# DTMF.net
KiCad netlist of a schematic drawn in Altium Designer
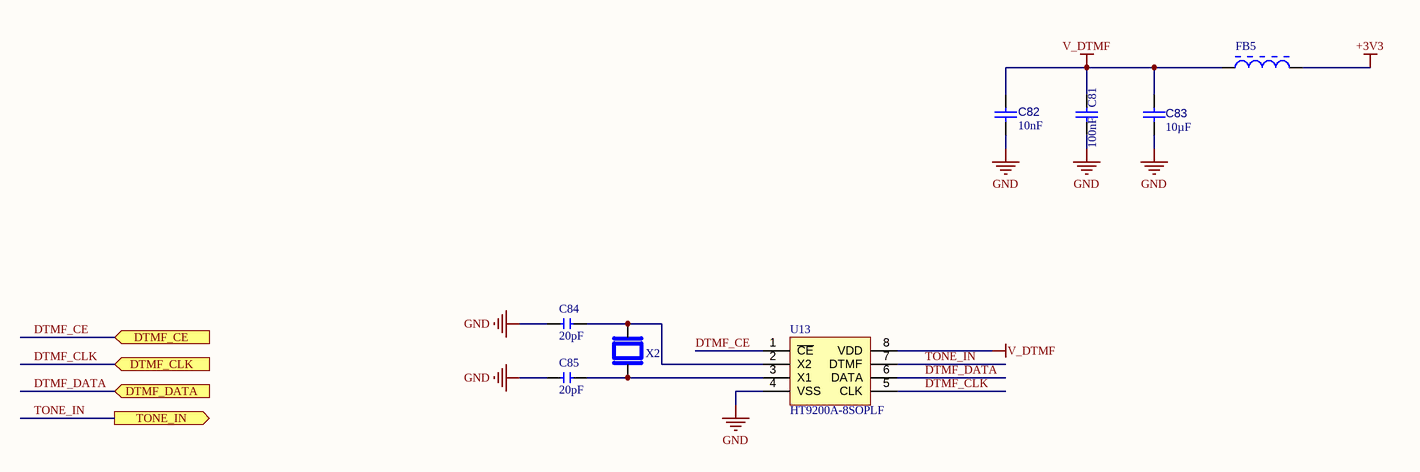
[diagram p0: DTMF.SchDoc]

(export (version "E")
  (design (tool "Eeschema 10.0.6"))
  (components
    (comp (ref "C81")
      (value "100nF")
      (footprint "C0603")
      (description "YAGEO - CC0603KRX7R8BB104 - CERAMIC CAPACITOR, 0.1UF, 25V, X7R, 10%, 0603, FULL REEL")
      (fields
        (field (name "TOLERANCE") "10%")
        (field (name "VOLTAGE") "25V")
        (field (name "SOURCE") "PTZLib.SchLib")
      )
      (libsource (lib "Kish Spark") (part "CAP-NP-2"))
    )
    (comp (ref "C82")
      (value "10nF")
      (footprint "C0603")
      (description "0603 10nF 50 V ±10 % Tolerance X7R Surface Mount Multilayer Ceramic Capacitor")
      (fields (field (name "TOLERANCE") "10%") (field (name "MANUFACTURER") "Kyocera AVX"))
      (libsource (lib "Kish Spark") (part "CAP-NP-2"))
    )
    (comp (ref "C83")
      (value "10µF")
      (footprint "0805")
      (description "Ceramic Capacitor, 10UF, 6.3V, X5R, 10%, 0805, Full Reel")
      (fields
        (field (name "MANUFACTURER") "KEMET")
        (field (name "MANUFACTURER PART NUMBER") "C0805C106K9PACTU")
      )
      (libsource (lib "Kish Spark") (part "CAP-NP-2"))
    )
    (comp (ref "C84")
      (value "20pF")
      (footprint "0805")
      (description "CAP CER 20PF 50V NPO 0805")
      (fields
        (field (name "MANUFACTURER") "Yageo")
        (field (name "MANUFACTURER PART NUMBER") "CC0805JRNPO9BN200")
      )
      (libsource (lib "Kish Spark") (part "CC0805JRNPO9BN200"))
    )
    (comp (ref "C85")
      (value "20pF")
      (footprint "0805")
      (description "CAP CER 20PF 50V NPO 0805")
      (fields
        (field (name "MANUFACTURER") "Yageo")
        (field (name "MANUFACTURER PART NUMBER") "CC0805JRNPO9BN200")
      )
      (libsource (lib "Kish Spark") (part "CC0805JRNPO9BN200"))
    )
    (comp (ref "FB5")
      (value "CMP-006-00051-1")
      (footprint "R0603")
      (description "Ferrite Beads 0603 60ohm")
      (fields (field (name "TOLERANCE") "25%") (field (name "SOURCE") "PTZLib.SchLib"))
      (libsource (lib "Kish Spark") (part "FerriteBead"))
    )
    (comp (ref "U13")
      (value "HT9200A-8SOPLF")
      (footprint "SSOIC8")
      (description "IC, Dtmf Generator, SMD, SOP8")
      (fields (field (name "MANUFACTURER") "Holtek"))
      (libsource (lib "Kish Spark") (part "HT9200A-8SOPLF"))
    )
    (comp (ref "X2")
      (value "CMP-003-00038-1")
      (footprint "XTAL")
      (description "Crystal 3.579545MHz ±30ppm (Tol) ±50ppm (Stability) 18pF FUND 180Ohm 2-Pin HC-49/US SMD T/R")
      (fields
        (field (name "MANUFACTURER") "Abracon")
        (field (name "MANUFACTURER PART NUMBER") "ABLS-3.579545MHZ-B4-T")
      )
      (libsource (lib "Kish Spark") (part "ABLS-3.579545MHZ-B4-T"))
    )
  )
  (nets
    (net (code "1") (name "+3V3") (class "Default")
      (node (ref "FB5") (pin "2") (pinfunction "2_2") (pintype "passive"))
    )
    (net (code "2") (name "/DTMF_CE") (class "Default")
      (node (ref "U13") (pin "1") (pinfunction "~{CE}_1") (pintype "passive"))
    )
    (net (code "3") (name "/DTMF_CLK") (class "Default")
      (node (ref "U13") (pin "5") (pinfunction "CLK_5") (pintype "passive"))
    )
    (net (code "4") (name "/DTMF_DATA") (class "Default")
      (node (ref "U13") (pin "6") (pinfunction "DATA_6") (pintype "passive"))
    )
    (net (code "5") (name "/TONE_IN") (class "Default")
      (node (ref "U13") (pin "7") (pinfunction "DTMF_7") (pintype "passive"))
    )
    (net (code "6") (name "GND") (class "Default")
      (node (ref "C81") (pin "2") (pinfunction "2_2") (pintype "passive"))
      (node (ref "C82") (pin "2") (pinfunction "2_2") (pintype "passive"))
      (node (ref "C83") (pin "1") (pinfunction "1_1") (pintype "passive"))
      (node (ref "C84") (pin "1") (pinfunction "1_1") (pintype "passive"))
      (node (ref "C85") (pin "1") (pinfunction "1_1") (pintype "passive"))
      (node (ref "U13") (pin "4") (pinfunction "VSS_4") (pintype "passive"))
    )
    (net (code "7") (name "Net-(U13-X1)") (class "Default")
      (node (ref "C85") (pin "2") (pinfunction "2_2") (pintype "passive"))
      (node (ref "U13") (pin "3") (pinfunction "X1_3") (pintype "passive"))
      (node (ref "X2") (pin "1") (pinfunction "1_1") (pintype "passive"))
    )
    (net (code "8") (name "Net-(U13-X2)") (class "Default")
      (node (ref "C84") (pin "2") (pinfunction "2_2") (pintype "passive"))
      (node (ref "U13") (pin "2") (pinfunction "X2_2") (pintype "passive"))
      (node (ref "X2") (pin "2") (pinfunction "2_2") (pintype "passive"))
    )
    (net (code "9") (name "V_DTMF") (class "Default")
      (node (ref "C81") (pin "1") (pinfunction "1_1") (pintype "passive"))
      (node (ref "C82") (pin "1") (pinfunction "1_1") (pintype "passive"))
      (node (ref "C83") (pin "2") (pinfunction "2_2") (pintype "passive"))
      (node (ref "FB5") (pin "1") (pinfunction "1_1") (pintype "passive"))
      (node (ref "U13") (pin "8") (pinfunction "VDD_8") (pintype "passive"))
    )
  )
)
